# SCH_NFC-CARD_2025-11-08.net
KiCad netlist of a schematic drawn in EasyEDA
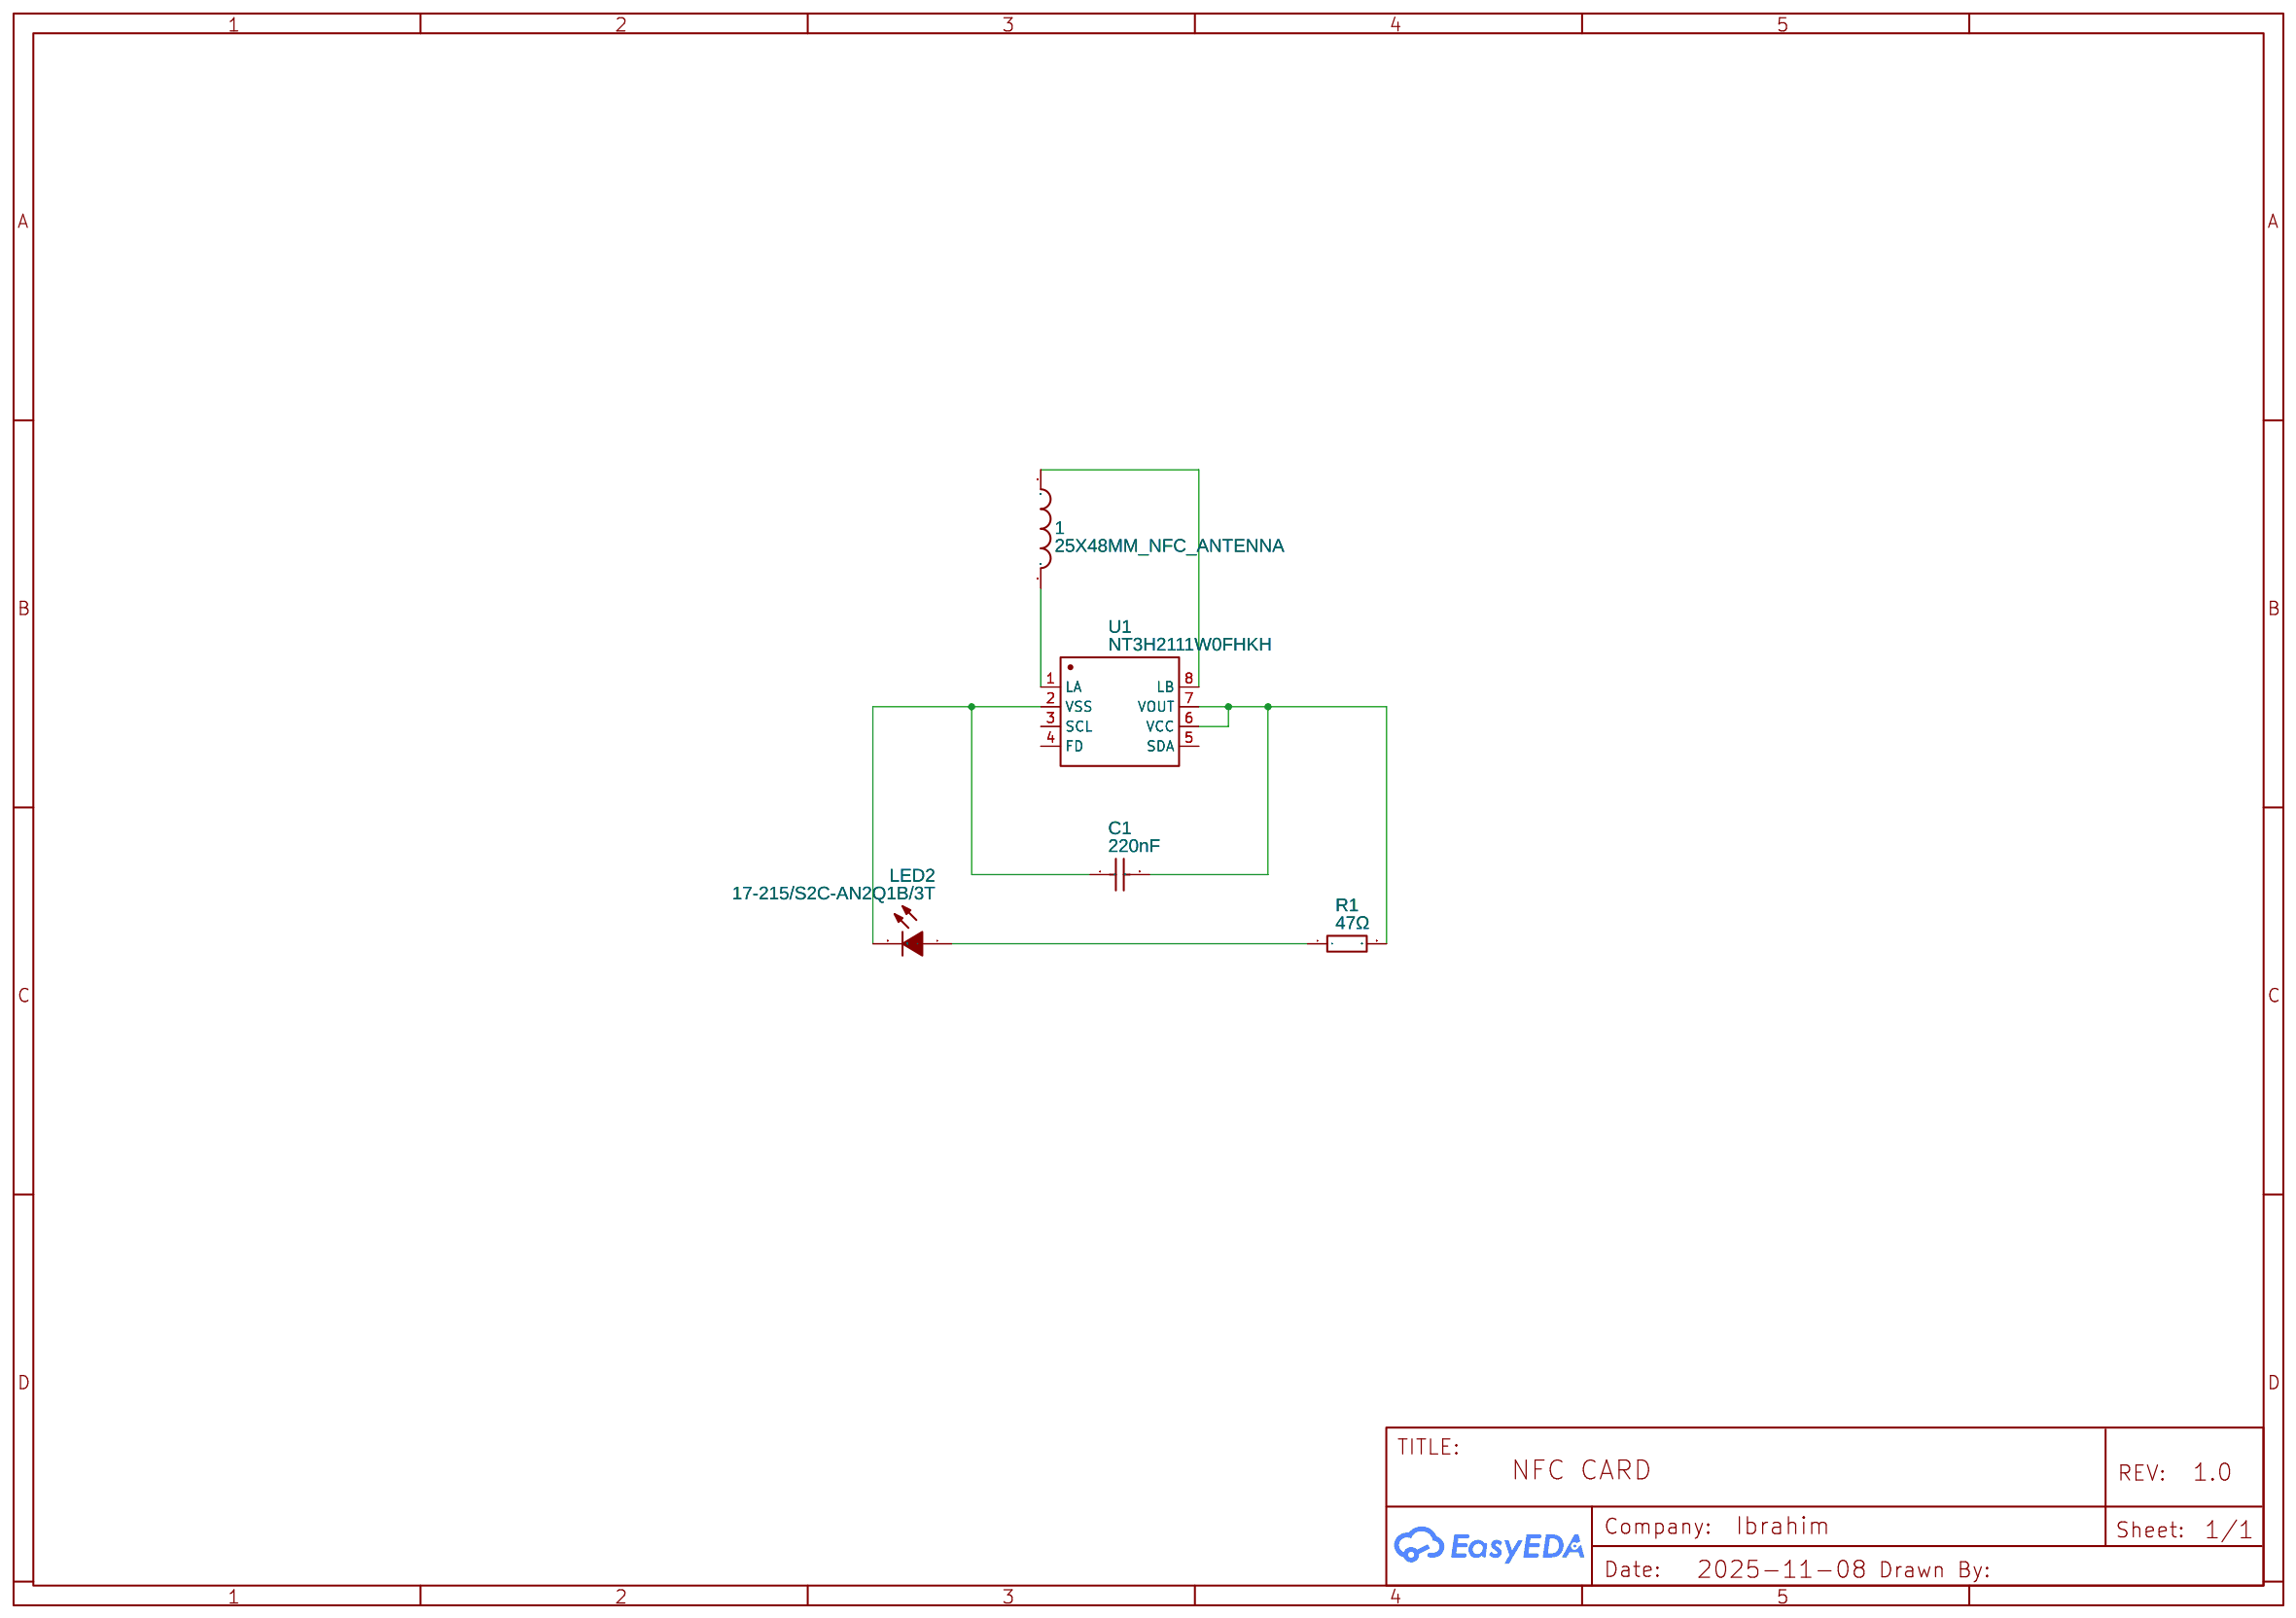
[diagram p0: schematic sheet]

(export (version "E")
  (design (tool "Eeschema 10.0.6"))
  (components
    (comp (ref "1") (value "25X48MM_NFC_ANTENNA") (libsource (lib "") (part "25X48MM_NFC_ANTENNA")))
    (comp (ref "C1")
      (value "220nF")
      (fields
        (field (name "Manufacturer Part") "CL10B224KA8NNNC")
        (field (name "Manufacturer") "SAMSUNG(三星)")
      )
      (libsource (lib "") (part "CL10B224KA8NNNC"))
    )
    (comp (ref "LED2")
      (value "17-215/S2C-AN2Q1B/3T")
      (fields (field (name "Manufacturer") "EVERLIGHT(亿光)"))
      (libsource (lib "") (part "17-215/S2C-AN2Q1B/3T"))
    )
    (comp (ref "R1")
      (value "47Ω")
      (fields
        (field (name "Manufacturer Part") "0603WAF470JT5E")
        (field (name "Manufacturer") "UNI-ROYAL(厚声)")
      )
      (libsource (lib "") (part "0603WAF470JT5E"))
    )
    (comp (ref "U1")
      (value "NT3H2111W0FHKH")
      (fields (field (name "Manufacturer") "NXP(恩智浦)"))
      (libsource (lib "") (part "NT3H2111W0FHKH"))
    )
  )
  (nets
    (net (code "1") (name "Net-(LED2-A)") (class "Default")
      (node (ref "LED2") (pin "1") (pinfunction "A_1") (pintype "input"))
      (node (ref "R1") (pin "1") (pinfunction "1_1") (pintype "input"))
    )
    (net (code "2") (name "Net-(LED2-C)") (class "Default")
      (node (ref "C1") (pin "1") (pinfunction "1_1") (pintype "input"))
      (node (ref "LED2") (pin "2") (pinfunction "C_2") (pintype "input"))
      (node (ref "U1") (pin "2") (pinfunction "VSS_2") (pintype "unspecified"))
    )
    (net (code "3") (name "Net-(U1-LA)") (class "Default")
      (node (ref "1") (pin "P$2") (pinfunction "P$2_P$2") (pintype "bidirectional"))
      (node (ref "U1") (pin "1") (pinfunction "LA_1") (pintype "unspecified"))
    )
    (net (code "4") (name "Net-(U1-LB)") (class "Default")
      (node (ref "1") (pin "P$1") (pinfunction "P$1_P$1") (pintype "bidirectional"))
      (node (ref "U1") (pin "8") (pinfunction "LB_8") (pintype "unspecified"))
    )
    (net (code "5") (name "Net-(U1-VCC)") (class "Default")
      (node (ref "C1") (pin "2") (pinfunction "2_2") (pintype "input"))
      (node (ref "R1") (pin "2") (pinfunction "2_2") (pintype "input"))
      (node (ref "U1") (pin "6") (pinfunction "VCC_6") (pintype "unspecified"))
      (node (ref "U1") (pin "7") (pinfunction "VOUT_7") (pintype "unspecified"))
    )
    (net (code "6") (name "unconnected-(U1-FD-Pad4)") (class "Default")
      (node (ref "U1") (pin "4") (pinfunction "FD_4") (pintype "unspecified"))
    )
    (net (code "7") (name "unconnected-(U1-SCL-Pad3)") (class "Default")
      (node (ref "U1") (pin "3") (pinfunction "SCL_3") (pintype "unspecified"))
    )
    (net (code "8") (name "unconnected-(U1-SDA-Pad5)") (class "Default")
      (node (ref "U1") (pin "5") (pinfunction "SDA_5") (pintype "unspecified"))
    )
  )
)
